# lemon-drop.net
KiCad netlist of a schematic drawn in EAGLE
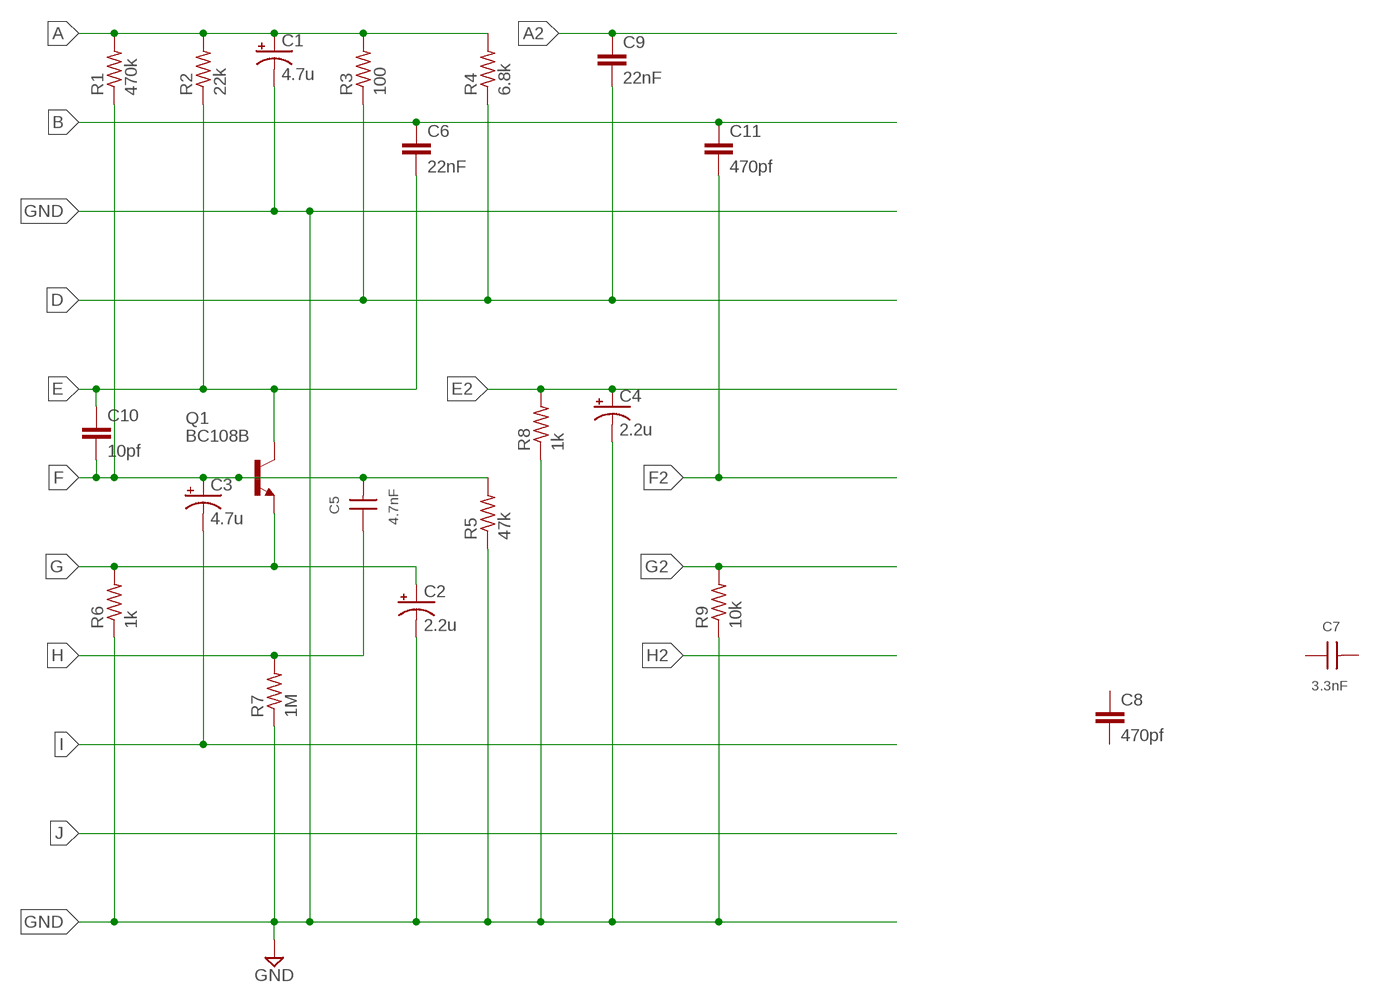
[diagram p0: schematic, sheet 1]

(export (version "E")
  (design (tool "Eeschema 10.0.6"))
  (components
    (comp (ref "C1")
      (value "4.7u")
      (footprint "eagle-import:C-E-0.1_0.15")
      (libsource (lib "eagle-import") (part "C-E0.1_0.15"))
    )
    (comp (ref "C2")
      (value "2.2u")
      (footprint "eagle-import:C-E-0.1_0.15")
      (libsource (lib "eagle-import") (part "C-E0.1_0.15"))
    )
    (comp (ref "C3")
      (value "4.7u")
      (footprint "eagle-import:C-E-0.1_0.15")
      (libsource (lib "eagle-import") (part "C-E0.1_0.15"))
    )
    (comp (ref "C4")
      (value "2.2u")
      (footprint "eagle-import:C-E-0.1_0.15")
      (libsource (lib "eagle-import") (part "C-E0.1_0.15"))
    )
    (comp (ref "C5")
      (value "4.7nF")
      (footprint "eagle-import:C-PP-0.4_0.2")
      (libsource (lib "eagle-import") (part "C-PP_0.40.2"))
    )
    (comp (ref "C6")
      (value "22nF")
      (footprint "eagle-import:C7.5B5")
      (libsource (lib "eagle-import") (part "C7.5/5"))
    )
    (comp (ref "C7")
      (value "3.3nF")
      (footprint "eagle-import:C-PP-0.4_0.15")
      (libsource (lib "eagle-import") (part "C-PP_0.40.15"))
    )
    (comp (ref "C8")
      (value "470pf")
      (footprint "eagle-import:C-C-0.1_0.05")
      (libsource (lib "eagle-import") (part "C-CERAMICC-C-0.1_0.05"))
    )
    (comp (ref "C9")
      (value "22nF")
      (footprint "eagle-import:C7.5B5")
      (libsource (lib "eagle-import") (part "C7.5/5"))
    )
    (comp (ref "C10")
      (value "10pf")
      (footprint "eagle-import:C-C-0.1_0.05")
      (libsource (lib "eagle-import") (part "C-CERAMICC-C-0.1_0.05"))
    )
    (comp (ref "C11")
      (value "470pf")
      (footprint "eagle-import:C-C-0.1_0.05")
      (libsource (lib "eagle-import") (part "C-CERAMICC-C-0.1_0.05"))
    )
    (comp (ref "Q1")
      (value "BC108B")
      (footprint "eagle-import:TO18")
      (libsource (lib "eagle-import") (part "BC108B"))
    )
    (comp (ref "R1")
      (value "470k")
      (footprint "eagle-import:0204_7")
      (libsource (lib "eagle-import") (part "RESISTOR0204/7"))
    )
    (comp (ref "R2")
      (value "22k")
      (footprint "eagle-import:0204_7")
      (libsource (lib "eagle-import") (part "RESISTOR0204/7"))
    )
    (comp (ref "R3")
      (value "100")
      (footprint "eagle-import:0204_7")
      (libsource (lib "eagle-import") (part "RESISTOR0204/7"))
    )
    (comp (ref "R4")
      (value "6.8k")
      (footprint "eagle-import:0204_7")
      (libsource (lib "eagle-import") (part "RESISTOR0204/7"))
    )
    (comp (ref "R5")
      (value "47k")
      (footprint "eagle-import:0204_7")
      (libsource (lib "eagle-import") (part "RESISTOR0204/7"))
    )
    (comp (ref "R6")
      (value "1k")
      (footprint "eagle-import:0204_7")
      (libsource (lib "eagle-import") (part "RESISTOR0204/7"))
    )
    (comp (ref "R7")
      (value "1M")
      (footprint "eagle-import:0204_7")
      (libsource (lib "eagle-import") (part "RESISTOR0204/7"))
    )
    (comp (ref "R8")
      (value "1k")
      (footprint "eagle-import:0204_7")
      (libsource (lib "eagle-import") (part "RESISTOR0204/7"))
    )
    (comp (ref "R9")
      (value "10k")
      (footprint "eagle-import:0204_7")
      (libsource (lib "eagle-import") (part "RESISTOR0204/7"))
    )
  )
  (nets
    (net (code "1") (name "A") (class "Default")
      (node (ref "C1") (pin "+") (pinfunction "+_+") (pintype "passive"))
      (node (ref "R1") (pin "2") (pinfunction "2_2") (pintype "passive"))
      (node (ref "R2") (pin "2") (pinfunction "2_2") (pintype "passive"))
      (node (ref "R3") (pin "2") (pinfunction "2_2") (pintype "passive"))
      (node (ref "R4") (pin "2") (pinfunction "2_2") (pintype "passive"))
    )
    (net (code "2") (name "A2") (class "Default")
      (node (ref "C9") (pin "1") (pinfunction "1_1") (pintype "passive"))
    )
    (net (code "3") (name "B") (class "Default")
      (node (ref "C11") (pin "1") (pinfunction "1_1") (pintype "passive"))
      (node (ref "C6") (pin "1") (pinfunction "1_1") (pintype "passive"))
    )
    (net (code "4") (name "D") (class "Default")
      (node (ref "C9") (pin "2") (pinfunction "2_2") (pintype "passive"))
      (node (ref "R3") (pin "1") (pinfunction "1_1") (pintype "passive"))
      (node (ref "R4") (pin "1") (pinfunction "1_1") (pintype "passive"))
    )
    (net (code "5") (name "E") (class "Default")
      (node (ref "C10") (pin "1") (pinfunction "1_1") (pintype "passive"))
      (node (ref "C6") (pin "2") (pinfunction "2_2") (pintype "passive"))
      (node (ref "Q1") (pin "3") (pinfunction "C_3") (pintype "passive"))
      (node (ref "R2") (pin "1") (pinfunction "1_1") (pintype "passive"))
    )
    (net (code "6") (name "E2") (class "Default")
      (node (ref "C4") (pin "+") (pinfunction "+_+") (pintype "passive"))
      (node (ref "R8") (pin "2") (pinfunction "2_2") (pintype "passive"))
    )
    (net (code "7") (name "F") (class "Default")
      (node (ref "C10") (pin "2") (pinfunction "2_2") (pintype "passive"))
      (node (ref "C3") (pin "+") (pinfunction "+_+") (pintype "passive"))
      (node (ref "C5") (pin "2") (pinfunction "2_2") (pintype "passive"))
      (node (ref "Q1") (pin "2") (pinfunction "B_2") (pintype "passive"))
      (node (ref "R1") (pin "1") (pinfunction "1_1") (pintype "passive"))
      (node (ref "R5") (pin "2") (pinfunction "2_2") (pintype "passive"))
    )
    (net (code "8") (name "F2") (class "Default")
      (node (ref "C11") (pin "2") (pinfunction "2_2") (pintype "passive"))
    )
    (net (code "9") (name "G") (class "Default")
      (node (ref "C2") (pin "+") (pinfunction "+_+") (pintype "passive"))
      (node (ref "Q1") (pin "1") (pinfunction "E_1") (pintype "passive"))
      (node (ref "R6") (pin "2") (pinfunction "2_2") (pintype "passive"))
    )
    (net (code "10") (name "G2") (class "Default")
      (node (ref "R9") (pin "2") (pinfunction "2_2") (pintype "passive"))
    )
    (net (code "11") (name "GND") (class "Default")
      (node (ref "C1") (pin "-") (pinfunction "-_-") (pintype "passive"))
      (node (ref "C2") (pin "-") (pinfunction "-_-") (pintype "passive"))
      (node (ref "C4") (pin "-") (pinfunction "-_-") (pintype "passive"))
      (node (ref "R5") (pin "1") (pinfunction "1_1") (pintype "passive"))
      (node (ref "R6") (pin "1") (pinfunction "1_1") (pintype "passive"))
      (node (ref "R7") (pin "1") (pinfunction "1_1") (pintype "passive"))
      (node (ref "R8") (pin "1") (pinfunction "1_1") (pintype "passive"))
      (node (ref "R9") (pin "1") (pinfunction "1_1") (pintype "passive"))
    )
    (net (code "12") (name "H") (class "Default")
      (node (ref "C5") (pin "1") (pinfunction "1_1") (pintype "passive"))
      (node (ref "R7") (pin "2") (pinfunction "2_2") (pintype "passive"))
    )
    (net (code "14") (name "I") (class "Default")
      (node (ref "C3") (pin "-") (pinfunction "-_-") (pintype "passive"))
    )
    (net (code "16") (name "unconnected-(C7-Pad1)") (class "Default")
      (node (ref "C7") (pin "1") (pinfunction "1_1") (pintype "passive"))
    )
    (net (code "17") (name "unconnected-(C7-Pad2)") (class "Default")
      (node (ref "C7") (pin "2") (pinfunction "2_2") (pintype "passive"))
    )
    (net (code "18") (name "unconnected-(C8-Pad1)") (class "Default")
      (node (ref "C8") (pin "1") (pinfunction "1_1") (pintype "passive"))
    )
    (net (code "19") (name "unconnected-(C8-Pad2)") (class "Default")
      (node (ref "C8") (pin "2") (pinfunction "2_2") (pintype "passive"))
    )
  )
)
